# fetboard.net
KiCad netlist of a schematic drawn in EAGLE
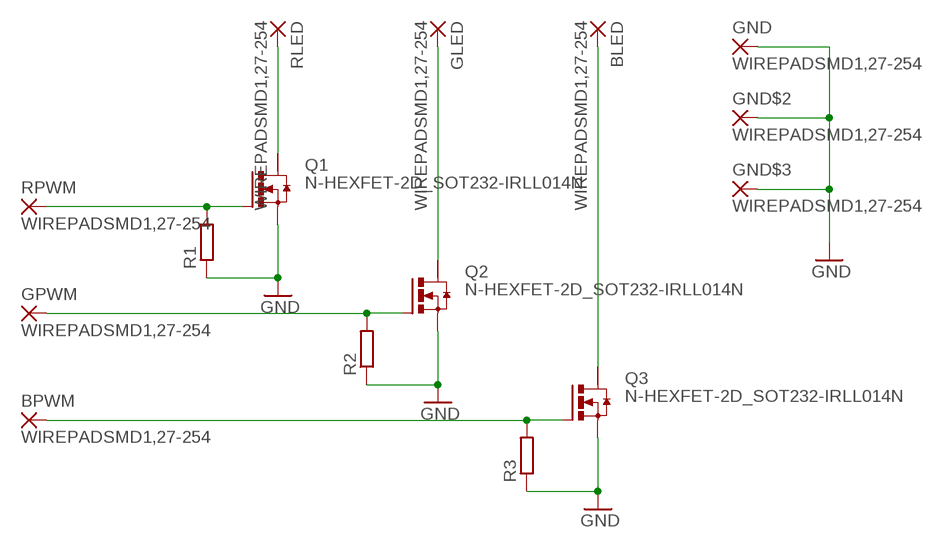
[diagram p0: schematic, sheet 1]

(export (version "E")
  (design (tool "Eeschema 10.0.6"))
  (components
    (comp (ref "BLED")
      (value "WIREPADSMD1,27-254")
      (footprint "eagle-import:SMD1,27-2,54")
      (libsource (lib "eagle-import") (part "WIREPADSMD1,27-254"))
    )
    (comp (ref "BPWM")
      (value "WIREPADSMD1,27-254")
      (footprint "eagle-import:SMD1,27-2,54")
      (libsource (lib "eagle-import") (part "WIREPADSMD1,27-254"))
    )
    (comp (ref "GLED")
      (value "WIREPADSMD1,27-254")
      (footprint "eagle-import:SMD1,27-2,54")
      (libsource (lib "eagle-import") (part "WIREPADSMD1,27-254"))
    )
    (comp (ref "GND")
      (value "WIREPADSMD1,27-254")
      (footprint "eagle-import:SMD1,27-2,54")
      (libsource (lib "eagle-import") (part "WIREPADSMD1,27-254"))
    )
    (comp (ref "GND$2")
      (value "WIREPADSMD1,27-254")
      (footprint "eagle-import:SMD1,27-2,54")
      (libsource (lib "eagle-import") (part "WIREPADSMD1,27-254"))
    )
    (comp (ref "GND$3")
      (value "WIREPADSMD1,27-254")
      (footprint "eagle-import:SMD1,27-2,54")
      (libsource (lib "eagle-import") (part "WIREPADSMD1,27-254"))
    )
    (comp (ref "GPWM")
      (value "WIREPADSMD1,27-254")
      (footprint "eagle-import:SMD1,27-2,54")
      (libsource (lib "eagle-import") (part "WIREPADSMD1,27-254"))
    )
    (comp (ref "Q1")
      (value "N-HEXFET-2D_SOT232-IRLL014N")
      (footprint "eagle-import:SOT223")
      (libsource (lib "eagle-import") (part "N-HEXFET-2D_?-SOT232IRLL014N"))
    )
    (comp (ref "Q2")
      (value "N-HEXFET-2D_SOT232-IRLL014N")
      (footprint "eagle-import:SOT223")
      (libsource (lib "eagle-import") (part "N-HEXFET-2D_?-SOT232IRLL014N"))
    )
    (comp (ref "Q3")
      (value "N-HEXFET-2D_SOT232-IRLL014N")
      (footprint "eagle-import:SOT223")
      (libsource (lib "eagle-import") (part "N-HEXFET-2D_?-SOT232IRLL014N"))
    )
    (comp (ref "R1")
      (value "R-EU_R1206")
      (footprint "eagle-import:R1206")
      (libsource (lib "eagle-import") (part "R-EU_R1206"))
    )
    (comp (ref "R2")
      (value "R-EU_R1206")
      (footprint "eagle-import:R1206")
      (libsource (lib "eagle-import") (part "R-EU_R1206"))
    )
    (comp (ref "R3")
      (value "R-EU_R1206")
      (footprint "eagle-import:R1206")
      (libsource (lib "eagle-import") (part "R-EU_R1206"))
    )
    (comp (ref "RLED")
      (value "WIREPADSMD1,27-254")
      (footprint "eagle-import:SMD1,27-2,54")
      (libsource (lib "eagle-import") (part "WIREPADSMD1,27-254"))
    )
    (comp (ref "RPWM")
      (value "WIREPADSMD1,27-254")
      (footprint "eagle-import:SMD1,27-2,54")
      (libsource (lib "eagle-import") (part "WIREPADSMD1,27-254"))
    )
  )
  (nets
    (net (code "1") (name "GND") (class "Default")
      (node (ref "GND") (pin "1") (pinfunction "P_1") (pintype "passive"))
      (node (ref "GND$2") (pin "1") (pinfunction "P_1") (pintype "passive"))
      (node (ref "GND$3") (pin "1") (pinfunction "P_1") (pintype "passive"))
      (node (ref "Q1") (pin "3") (pinfunction "S_3") (pintype "passive"))
      (node (ref "Q2") (pin "3") (pinfunction "S_3") (pintype "passive"))
      (node (ref "Q3") (pin "3") (pinfunction "S_3") (pintype "passive"))
      (node (ref "R1") (pin "1") (pinfunction "1_1") (pintype "passive"))
      (node (ref "R2") (pin "1") (pinfunction "1_1") (pintype "passive"))
      (node (ref "R3") (pin "1") (pinfunction "1_1") (pintype "passive"))
    )
    (net (code "2") (name "Net-(BLED-P)") (class "Default")
      (node (ref "BLED") (pin "1") (pinfunction "P_1") (pintype "passive"))
      (node (ref "Q3") (pin "2") (pinfunction "D_2") (pintype "passive"))
    )
    (net (code "3") (name "Net-(BPWM-P)") (class "Default")
      (node (ref "BPWM") (pin "1") (pinfunction "P_1") (pintype "passive"))
      (node (ref "Q3") (pin "1") (pinfunction "G_1") (pintype "passive"))
      (node (ref "R3") (pin "2") (pinfunction "2_2") (pintype "passive"))
    )
    (net (code "4") (name "Net-(GLED-P)") (class "Default")
      (node (ref "GLED") (pin "1") (pinfunction "P_1") (pintype "passive"))
      (node (ref "Q2") (pin "2") (pinfunction "D_2") (pintype "passive"))
    )
    (net (code "5") (name "Net-(GPWM-P)") (class "Default")
      (node (ref "GPWM") (pin "1") (pinfunction "P_1") (pintype "passive"))
      (node (ref "Q2") (pin "1") (pinfunction "G_1") (pintype "passive"))
      (node (ref "R2") (pin "2") (pinfunction "2_2") (pintype "passive"))
    )
    (net (code "6") (name "Net-(Q1-G)") (class "Default")
      (node (ref "Q1") (pin "1") (pinfunction "G_1") (pintype "passive"))
      (node (ref "R1") (pin "2") (pinfunction "2_2") (pintype "passive"))
      (node (ref "RPWM") (pin "1") (pinfunction "P_1") (pintype "passive"))
    )
    (net (code "7") (name "Net-(RLED-P)") (class "Default")
      (node (ref "Q1") (pin "2") (pinfunction "D_2") (pintype "passive"))
      (node (ref "RLED") (pin "1") (pinfunction "P_1") (pintype "passive"))
    )
    (net (code "8") (name "unconnected-(Q1-D-Pad4)") (class "Default")
      (node (ref "Q1") (pin "4") (pinfunction "D_4") (pintype "passive"))
    )
    (net (code "9") (name "unconnected-(Q2-D-Pad4)") (class "Default")
      (node (ref "Q2") (pin "4") (pinfunction "D_4") (pintype "passive"))
    )
    (net (code "10") (name "unconnected-(Q3-D-Pad4)") (class "Default")
      (node (ref "Q3") (pin "4") (pinfunction "D_4") (pintype "passive"))
    )
  )
)
